# power_supply.net
KiCad netlist of a schematic drawn in EAGLE
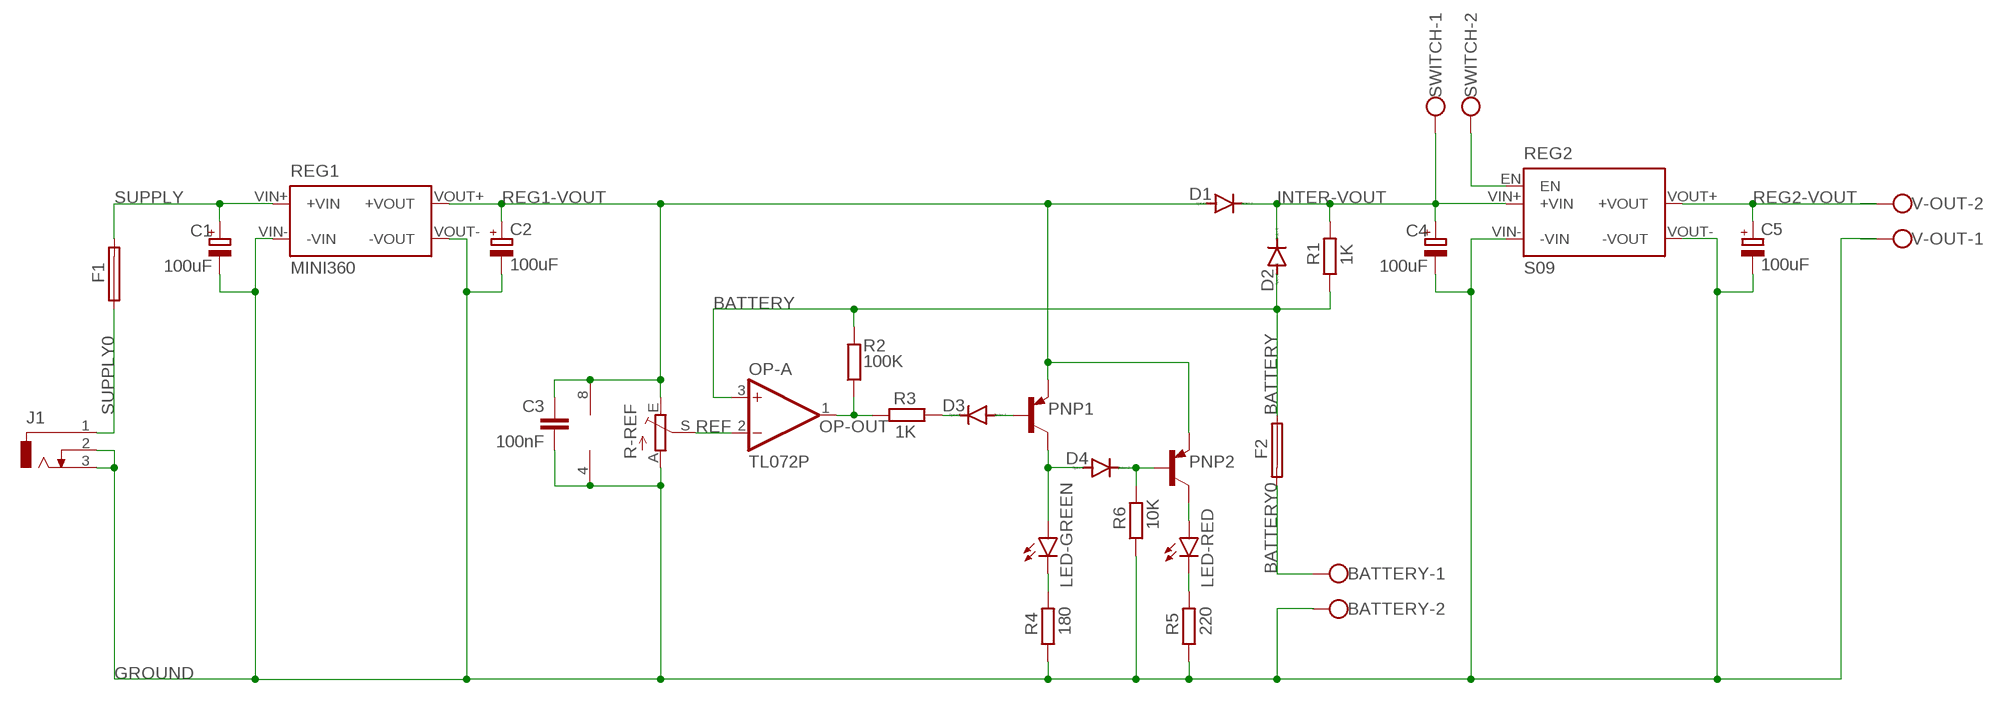
[diagram p0: schematic, sheet 1]

(export (version "E")
  (design (tool "Eeschema 10.0.6"))
  (components
    (comp (ref "BATTERY")
      (value "W237-102")
      (footprint "eagle-import:W237-102")
      (fields (field (name "MPN") "237-102"))
      (libsource (lib "eagle-import") (part "W237-102"))
    )
    (comp (ref "C1")
      (value "100uF")
      (footprint "eagle-import:E5-6")
      (libsource (lib "eagle-import") (part "CPOL-EUE5-6"))
    )
    (comp (ref "C2")
      (value "100uF")
      (footprint "eagle-import:E5-6")
      (libsource (lib "eagle-import") (part "CPOL-EUE5-6"))
    )
    (comp (ref "C3")
      (value "100nF")
      (footprint "eagle-import:C5B2.5")
      (libsource (lib "eagle-import") (part "C5/2.5"))
    )
    (comp (ref "C4")
      (value "100uF")
      (footprint "eagle-import:E2-5")
      (libsource (lib "eagle-import") (part "CPOL-EUE2-5"))
    )
    (comp (ref "C5")
      (value "100uF")
      (footprint "eagle-import:E2-5")
      (libsource (lib "eagle-import") (part "CPOL-EUE2-5"))
    )
    (comp (ref "D1")
      (value "BAS15")
      (footprint "eagle-import:DO34-7")
      (libsource (lib "eagle-import") (part "BAS15"))
    )
    (comp (ref "D2")
      (value "BAS15")
      (footprint "eagle-import:DO34-7")
      (libsource (lib "eagle-import") (part "BAS15"))
    )
    (comp (ref "D3")
      (value "BAS15")
      (footprint "eagle-import:DO34-7")
      (libsource (lib "eagle-import") (part "BAS15"))
    )
    (comp (ref "D4")
      (value "BAS15")
      (footprint "eagle-import:DO34-7")
      (libsource (lib "eagle-import") (part "BAS15"))
    )
    (comp (ref "F1")
      (value "SH22,5")
      (footprint "eagle-import:SH22,5")
      (fields (field (name "MF") "SCHURTER") (field (name "MPN") "0031.8201"))
      (libsource (lib "eagle-import") (part "SH22,5"))
    )
    (comp (ref "F2")
      (value "SH22,5")
      (footprint "eagle-import:SH22,5")
      (fields (field (name "MF") "SCHURTER") (field (name "MPN") "0031.8201"))
      (libsource (lib "eagle-import") (part "SH22,5"))
    )
    (comp (ref "J1")
      (value "DCJ0303")
      (footprint "eagle-import:DCJ0303")
      (libsource (lib "eagle-import") (part "DCJ0303"))
    )
    (comp (ref "LED-GREEN")
      (value "LED5MM")
      (footprint "eagle-import:LED5MM")
      (libsource (lib "eagle-import") (part "LED5MM"))
    )
    (comp (ref "LED-RED")
      (value "LED5MM")
      (footprint "eagle-import:LED5MM")
      (libsource (lib "eagle-import") (part "LED5MM"))
    )
    (comp (ref "OP-")
      (value "TL072P")
      (footprint "eagle-import:DIL08")
      (libsource (lib "eagle-import") (part "TL072P"))
    )
    (comp (ref "PNP1")
      (value "BC557A-PNP-TO92-EBC")
      (footprint "eagle-import:TO92-EBC")
      (libsource (lib "eagle-import") (part "-PNP-TO92-EBCBC557A"))
    )
    (comp (ref "PNP2")
      (value "BC557A-PNP-TO92-EBC")
      (footprint "eagle-import:TO92-EBC")
      (libsource (lib "eagle-import") (part "-PNP-TO92-EBCBC557A"))
    )
    (comp (ref "R-REF")
      (value "TRIM_EU-PT10")
      (footprint "eagle-import:PT-10")
      (libsource (lib "eagle-import") (part "TRIM_EU-PT10"))
    )
    (comp (ref "R1")
      (value "1K")
      (footprint "eagle-import:0204_7")
      (libsource (lib "eagle-import") (part "R-EU_0204/7"))
    )
    (comp (ref "R2")
      (value "100K")
      (footprint "eagle-import:0204_7")
      (libsource (lib "eagle-import") (part "R-EU_0204/7"))
    )
    (comp (ref "R3")
      (value "1K")
      (footprint "eagle-import:0204_7")
      (libsource (lib "eagle-import") (part "R-EU_0204/7"))
    )
    (comp (ref "R4")
      (value "180")
      (footprint "eagle-import:0204_7")
      (libsource (lib "eagle-import") (part "R-EU_0204/7"))
    )
    (comp (ref "R5")
      (value "220")
      (footprint "eagle-import:0204_7")
      (libsource (lib "eagle-import") (part "R-EU_0204/7"))
    )
    (comp (ref "R6")
      (value "10K")
      (footprint "eagle-import:0204_7")
      (libsource (lib "eagle-import") (part "R-EU_0204/7"))
    )
    (comp (ref "REG1")
      (value "MINI360")
      (footprint "eagle-import:DC-DC-CONVERTER-MINI360")
      (libsource (lib "eagle-import") (part "MINI360"))
    )
    (comp (ref "REG2")
      (value "S09")
      (footprint "eagle-import:DC-DC-CONVERTER-S09")
      (libsource (lib "eagle-import") (part "S09"))
    )
    (comp (ref "SWITCH")
      (value "W237-102")
      (footprint "eagle-import:W237-102")
      (fields (field (name "MPN") "237-102"))
      (libsource (lib "eagle-import") (part "W237-102"))
    )
    (comp (ref "V-OUT")
      (value "W237-102")
      (footprint "eagle-import:W237-102")
      (fields (field (name "MPN") "237-102"))
      (libsource (lib "eagle-import") (part "W237-102"))
    )
  )
  (nets
    (net (code "1") (name "/BATTERY") (class "Default")
      (node (ref "D2") (pin "A") (pinfunction "A_A") (pintype "passive"))
      (node (ref "F2") (pin "1") (pinfunction "1_1") (pintype "passive"))
      (node (ref "OP-") (pin "3") (pinfunction "+IN_3") (pintype "input"))
      (node (ref "R1") (pin "1") (pinfunction "1_1") (pintype "passive"))
      (node (ref "R2") (pin "2") (pinfunction "2_2") (pintype "passive"))
    )
    (net (code "2") (name "/BATTERY0") (class "Default")
      (node (ref "BATTERY") (pin "1") (pinfunction "KL_1") (pintype "passive"))
      (node (ref "F2") (pin "2") (pinfunction "2_2") (pintype "passive"))
    )
    (net (code "3") (name "/GROUND") (class "Default")
      (node (ref "BATTERY") (pin "2") (pinfunction "KL_2") (pintype "passive"))
      (node (ref "C1") (pin "-") (pinfunction "-_-") (pintype "passive"))
      (node (ref "C2") (pin "-") (pinfunction "-_-") (pintype "passive"))
      (node (ref "C3") (pin "2") (pinfunction "2_2") (pintype "passive"))
      (node (ref "C4") (pin "-") (pinfunction "-_-") (pintype "passive"))
      (node (ref "C5") (pin "-") (pinfunction "-_-") (pintype "passive"))
      (node (ref "J1") (pin "2") (pinfunction "2_2") (pintype "passive"))
      (node (ref "J1") (pin "3") (pinfunction "3_3") (pintype "passive"))
      (node (ref "OP-") (pin "4") (pinfunction "V-_4") (pintype "power_in"))
      (node (ref "R-REF") (pin "A") (pinfunction "A_A") (pintype "passive"))
      (node (ref "R4") (pin "1") (pinfunction "1_1") (pintype "passive"))
      (node (ref "R5") (pin "1") (pinfunction "1_1") (pintype "passive"))
      (node (ref "R6") (pin "1") (pinfunction "1_1") (pintype "passive"))
      (node (ref "REG1") (pin "VIN-") (pinfunction "-VIN_VIN-") (pintype "passive"))
      (node (ref "REG1") (pin "VOUT-") (pinfunction "-VOUT_VOUT-") (pintype "passive"))
      (node (ref "REG2") (pin "VIN-") (pinfunction "-VIN_VIN-") (pintype "passive"))
      (node (ref "REG2") (pin "VOUT-") (pinfunction "-VOUT_VOUT-") (pintype "passive"))
      (node (ref "V-OUT") (pin "1") (pinfunction "KL_1") (pintype "passive"))
    )
    (net (code "4") (name "/INTER-VOUT") (class "Default")
      (node (ref "C4") (pin "+") (pinfunction "+_+") (pintype "passive"))
      (node (ref "D1") (pin "C") (pinfunction "C_C") (pintype "passive"))
      (node (ref "D2") (pin "C") (pinfunction "C_C") (pintype "passive"))
      (node (ref "R1") (pin "2") (pinfunction "2_2") (pintype "passive"))
      (node (ref "REG2") (pin "VIN+") (pinfunction "+VIN_VIN+") (pintype "passive"))
      (node (ref "SWITCH") (pin "1") (pinfunction "KL_1") (pintype "passive"))
    )
    (net (code "5") (name "/OP-OUT") (class "Default")
      (node (ref "OP-") (pin "1") (pinfunction "OUT_1") (pintype "output"))
      (node (ref "R2") (pin "1") (pinfunction "1_1") (pintype "passive"))
      (node (ref "R3") (pin "2") (pinfunction "2_2") (pintype "passive"))
    )
    (net (code "6") (name "/REF") (class "Default")
      (node (ref "OP-") (pin "2") (pinfunction "-IN_2") (pintype "input"))
      (node (ref "R-REF") (pin "S") (pinfunction "S_S") (pintype "passive"))
    )
    (net (code "7") (name "/REG1-VOUT") (class "Default")
      (node (ref "C2") (pin "+") (pinfunction "+_+") (pintype "passive"))
      (node (ref "C3") (pin "1") (pinfunction "1_1") (pintype "passive"))
      (node (ref "D1") (pin "A") (pinfunction "A_A") (pintype "passive"))
      (node (ref "OP-") (pin "8") (pinfunction "V+_8") (pintype "power_in"))
      (node (ref "PNP1") (pin "E") (pinfunction "E_E") (pintype "passive"))
      (node (ref "PNP2") (pin "E") (pinfunction "E_E") (pintype "passive"))
      (node (ref "R-REF") (pin "E") (pinfunction "E_E") (pintype "passive"))
      (node (ref "REG1") (pin "VOUT+") (pinfunction "+VOUT_VOUT+") (pintype "passive"))
    )
    (net (code "8") (name "/REG2-VOUT") (class "Default")
      (node (ref "C5") (pin "+") (pinfunction "+_+") (pintype "passive"))
      (node (ref "REG2") (pin "VOUT+") (pinfunction "+VOUT_VOUT+") (pintype "passive"))
      (node (ref "V-OUT") (pin "2") (pinfunction "KL_2") (pintype "passive"))
    )
    (net (code "9") (name "/SUPPLY") (class "Default")
      (node (ref "C1") (pin "+") (pinfunction "+_+") (pintype "passive"))
      (node (ref "F1") (pin "2") (pinfunction "2_2") (pintype "passive"))
      (node (ref "REG1") (pin "VIN+") (pinfunction "+VIN_VIN+") (pintype "passive"))
    )
    (net (code "10") (name "/SUPPLY0") (class "Default")
      (node (ref "F1") (pin "1") (pinfunction "1_1") (pintype "passive"))
      (node (ref "J1") (pin "1") (pinfunction "1_1") (pintype "passive"))
    )
    (net (code "11") (name "Net-(D3-PadA)") (class "Default")
      (node (ref "D3") (pin "A") (pinfunction "A_A") (pintype "passive"))
      (node (ref "PNP1") (pin "B") (pinfunction "B_B") (pintype "passive"))
    )
    (net (code "12") (name "Net-(D3-PadC)") (class "Default")
      (node (ref "D3") (pin "C") (pinfunction "C_C") (pintype "passive"))
      (node (ref "R3") (pin "1") (pinfunction "1_1") (pintype "passive"))
    )
    (net (code "13") (name "Net-(D4-PadA)") (class "Default")
      (node (ref "D4") (pin "A") (pinfunction "A_A") (pintype "passive"))
      (node (ref "LED-GREEN") (pin "A") (pinfunction "A_A") (pintype "passive"))
      (node (ref "PNP1") (pin "C") (pinfunction "C_C") (pintype "passive"))
    )
    (net (code "14") (name "Net-(D4-PadC)") (class "Default")
      (node (ref "D4") (pin "C") (pinfunction "C_C") (pintype "passive"))
      (node (ref "PNP2") (pin "B") (pinfunction "B_B") (pintype "passive"))
      (node (ref "R6") (pin "2") (pinfunction "2_2") (pintype "passive"))
    )
    (net (code "15") (name "Net-(LED-GREEN-C)") (class "Default")
      (node (ref "LED-GREEN") (pin "K") (pinfunction "C_K") (pintype "passive"))
      (node (ref "R4") (pin "2") (pinfunction "2_2") (pintype "passive"))
    )
    (net (code "16") (name "Net-(LED-RED-C)") (class "Default")
      (node (ref "LED-RED") (pin "K") (pinfunction "C_K") (pintype "passive"))
      (node (ref "R5") (pin "2") (pinfunction "2_2") (pintype "passive"))
    )
    (net (code "17") (name "Net-(LED-RED-PadA)") (class "Default")
      (node (ref "LED-RED") (pin "A") (pinfunction "A_A") (pintype "passive"))
      (node (ref "PNP2") (pin "C") (pinfunction "C_C") (pintype "passive"))
    )
    (net (code "18") (name "Net-(SWITCHB-KL)") (class "Default")
      (node (ref "REG2") (pin "EN") (pinfunction "EN_EN") (pintype "passive"))
      (node (ref "SWITCH") (pin "2") (pinfunction "KL_2") (pintype "passive"))
    )
  )
)
